# Trigger.net
KiCad netlist of a schematic drawn in Altium Designer
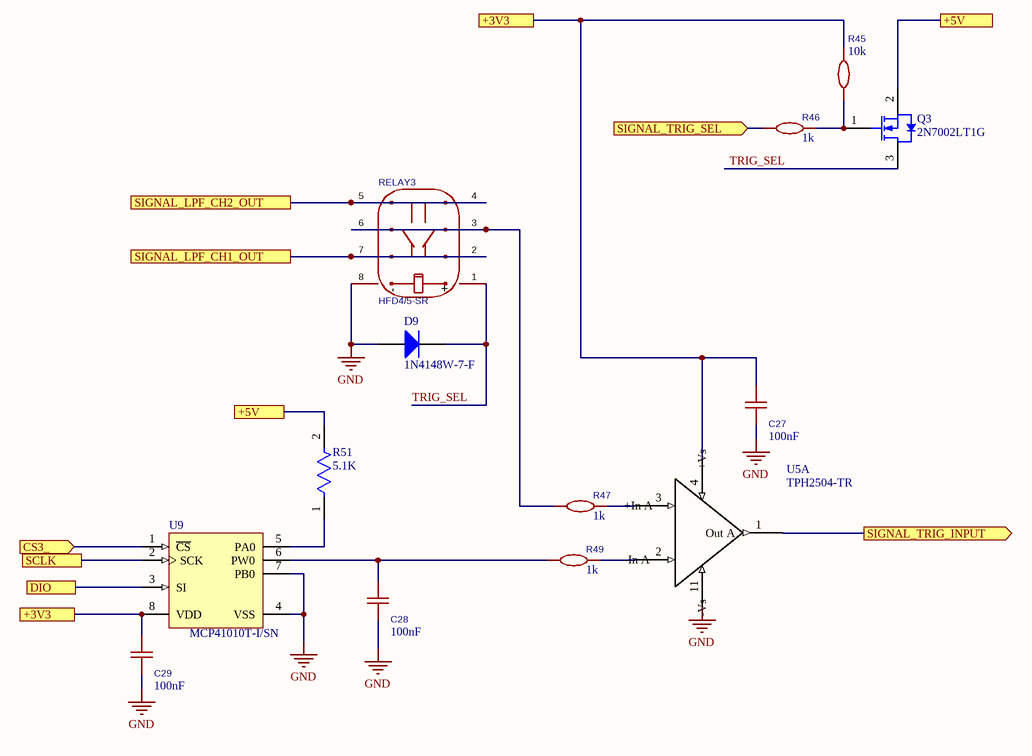
[diagram p0: Trigger.SchDoc]

(export (version "E")
  (design (tool "Eeschema 10.0.6"))
  (components
    (comp (ref "C27")
      (value "100nF")
      (footprint "C0805")
      (description "Capacitance:100nF Tolerance:±5% Tolerance:±5% Voltage Rating:50V Temperature Coefficient:X7R")
      (fields (field (name "MANUFACTURER") "YAGEO(国巨)") (field (name "TOLERANCE") "5%"))
      (libsource (lib "zhiming xue") (part "0805CG6R0C500NT_C67560"))
    )
    (comp (ref "C28")
      (value "100nF")
      (footprint "C0805")
      (description "Capacitance:100nF Tolerance:±5% Tolerance:±5% Voltage Rating:50V Temperature Coefficient:X7R")
      (fields (field (name "MANUFACTURER") "YAGEO(国巨)") (field (name "TOLERANCE") "5%"))
      (libsource (lib "zhiming xue") (part "0805CG6R0C500NT_C67560"))
    )
    (comp (ref "C29")
      (value "100nF")
      (footprint "C0805")
      (description "Capacitance:100nF Tolerance:±5% Tolerance:±5% Voltage Rating:50V Temperature Coefficient:X7R")
      (fields (field (name "MANUFACTURER") "YAGEO(国巨)") (field (name "TOLERANCE") "5%"))
      (libsource (lib "zhiming xue") (part "0805CG6R0C500NT_C67560"))
    )
    (comp (ref "D9")
      (value "1N4148W-7-F")
      (footprint "DIOD-SOD123-2_V")
      (description "Fast Switching Diode, 100 V, 0.15 A, -65 to 150 degC, 2-Pin?SOD123, RoHS, Tape and Reel")
      (fields (field (name "MANUFACTURER") "Diodes Inc"))
      (libsource (lib "Altium Content Vault") (part "D-AK-2"))
    )
    (comp (ref "Q3")
      (value "2N7002LT1G")
      (footprint "ONSC-SOT-23-3-318-08_V")
      (description "Small Signal MOSFET, 60 V, 115 mA, N-Channel, 3-Pin SOT-23, Pb-Free, Tape and Reel")
      (fields (field (name "MANUFACTURER") "On Semiconductor"))
      (libsource (lib "Altium Content Vault") (part "ONSC-NMOS-G1S2D3-3"))
    )
    (comp (ref "R45")
      (value "10k")
      (footprint "R0805")
      (fields
        (field (name "MANUFACTURER") "UNI-ROYAL(厚声)")
        (field (name "TOLERANCE") "1%")
        (field (name "MANUFACTURER PART NUMBER") "0805W8F1002T5E")
      )
      (libsource (lib "zhiming xue") (part "0805W8F0000T5E_C17477"))
    )
    (comp (ref "R46")
      (value "1k")
      (footprint "R0805")
      (fields
        (field (name "MANUFACTURER") "UNI-ROYAL(厚声)")
        (field (name "TOLERANCE") "1%")
        (field (name "MANUFACTURER PART NUMBER") "0805W8F1001T5E")
      )
      (libsource (lib "zhiming xue") (part "0805W8F0000T5E_C17477"))
    )
    (comp (ref "R47")
      (value "1k")
      (footprint "R0805")
      (fields
        (field (name "MANUFACTURER") "UNI-ROYAL(厚声)")
        (field (name "TOLERANCE") "1%")
        (field (name "MANUFACTURER PART NUMBER") "0805W8F1001T5E")
      )
      (libsource (lib "zhiming xue") (part "0805W8F0000T5E_C17477"))
    )
    (comp (ref "R49")
      (value "1k")
      (footprint "R0805")
      (fields
        (field (name "MANUFACTURER") "UNI-ROYAL(厚声)")
        (field (name "TOLERANCE") "1%")
        (field (name "MANUFACTURER PART NUMBER") "0805W8F1001T5E")
      )
      (libsource (lib "zhiming xue") (part "0805W8F0000T5E_C17477"))
    )
    (comp (ref "R51")
      (value "5.1K")
      (footprint "FP-RT0805-MFG")
      (description "125mW Thin Film Resistor ±50ppm/℃ ±1% 5.1kΩ 0805 Chip Resistor - Surface Mount ROHS")
      (fields (field (name "TOLERANCE") "1%"))
      (libsource (lib "zhiming xue") (part "1029c3af85768c4190bb7ad29bc67b5"))
    )
    (comp (ref "RELAY3")
      (value "HFD4/5-SR")
      (footprint "RELAY-SMD_HFD4-5-SR")
      (fields (field (name "MANUFACTURER") "HF(宏发)"))
      (libsource (lib "zhiming xue") (part "HFD4/5-SR"))
    )
    (comp (ref "U5")
      (value "TPH2504-TR")
      (footprint "TSOP65P640X120-14N")
      (description "Operational Amplifier, 4 Func, 5000uV Offset-Max, CMOS, PDSO14")
      (libsource (lib "zhiming xue") (part "TPH2504-TR-Symbol-1"))
    )
    (comp (ref "U9")
      (value "MCP41010T-I/SN")
      (footprint "SOIC-SN8_M")
      (libsource (lib "Altium Content Vault") (part "IN-DPOT-MCP41XXX-8"))
    )
  )
  (nets
    (net (code "1") (name "/+3V3") (class "Default")
      (node (ref "C27") (pin "1") (pinfunction "1_1") (pintype "passive"))
      (node (ref "C29") (pin "1") (pinfunction "1_1") (pintype "passive"))
      (node (ref "R45") (pin "2") (pinfunction "2_2") (pintype "passive"))
      (node (ref "U5") (pin "4") (pinfunction "+Vs_4") (pintype "input"))
      (node (ref "U9") (pin "8") (pinfunction "VDD_8") (pintype "power_in"))
    )
    (net (code "2") (name "/+5V") (class "Default")
      (node (ref "Q3") (pin "2") (pinfunction "S_2") (pintype "passive"))
      (node (ref "R51") (pin "2") (pinfunction "2_2") (pintype "passive"))
    )
    (net (code "3") (name "/CS3_") (class "Default")
      (node (ref "U9") (pin "1") (pinfunction "~{CS}_1") (pintype "input"))
    )
    (net (code "4") (name "/DIO") (class "Default")
      (node (ref "U9") (pin "3") (pinfunction "SI_3") (pintype "input"))
    )
    (net (code "5") (name "/SCLK") (class "Default")
      (node (ref "U9") (pin "2") (pinfunction "SCK_2") (pintype "input"))
    )
    (net (code "6") (name "/SIGNAL_LPF_CH1_OUT") (class "Default")
      (node (ref "RELAY3") (pin "2") (pinfunction "2_2") (pintype "passive"))
      (node (ref "RELAY3") (pin "7") (pinfunction "7_7") (pintype "passive"))
    )
    (net (code "7") (name "/SIGNAL_LPF_CH2_OUT") (class "Default")
      (node (ref "RELAY3") (pin "4") (pinfunction "4_4") (pintype "passive"))
      (node (ref "RELAY3") (pin "5") (pinfunction "5_5") (pintype "passive"))
    )
    (net (code "8") (name "/SIGNAL_TRIG_INPUT") (class "Default")
      (node (ref "U5") (pin "1") (pinfunction "Out_A_1") (pintype "output"))
    )
    (net (code "9") (name "/SIGNAL_TRIG_SEL") (class "Default")
      (node (ref "R46") (pin "1") (pinfunction "1_1") (pintype "passive"))
    )
    (net (code "10") (name "/TRIG_SEL") (class "Default")
      (node (ref "D9") (pin "2") (pinfunction "K_2") (pintype "passive"))
      (node (ref "Q3") (pin "3") (pinfunction "D_3") (pintype "passive"))
      (node (ref "RELAY3") (pin "1") (pinfunction "1_1") (pintype "passive"))
    )
    (net (code "11") (name "GND") (class "Default")
      (node (ref "C27") (pin "2") (pinfunction "2_2") (pintype "passive"))
      (node (ref "C28") (pin "2") (pinfunction "2_2") (pintype "passive"))
      (node (ref "C29") (pin "2") (pinfunction "2_2") (pintype "passive"))
      (node (ref "D9") (pin "1") (pinfunction "A_1") (pintype "passive"))
      (node (ref "RELAY3") (pin "8") (pinfunction "8_8") (pintype "passive"))
      (node (ref "U5") (pin "11") (pinfunction "-Vs_11") (pintype "input"))
      (node (ref "U9") (pin "4") (pinfunction "VSS_4") (pintype "power_in"))
      (node (ref "U9") (pin "7") (pinfunction "PB0_7") (pintype "passive"))
    )
    (net (code "12") (name "Net-(Q3-G)") (class "Default")
      (node (ref "Q3") (pin "1") (pinfunction "G_1") (pintype "passive"))
      (node (ref "R45") (pin "1") (pinfunction "1_1") (pintype "passive"))
      (node (ref "R46") (pin "2") (pinfunction "2_2") (pintype "passive"))
    )
    (net (code "13") (name "Net-(R47-Pad1)") (class "Default")
      (node (ref "R47") (pin "1") (pinfunction "1_1") (pintype "passive"))
      (node (ref "RELAY3") (pin "3") (pinfunction "3_3") (pintype "passive"))
      (node (ref "RELAY3") (pin "6") (pinfunction "6_6") (pintype "passive"))
    )
    (net (code "14") (name "Net-(U5A-+In_A)") (class "Default")
      (node (ref "R47") (pin "2") (pinfunction "2_2") (pintype "passive"))
      (node (ref "U5") (pin "3") (pinfunction "+In_A_3") (pintype "input"))
    )
    (net (code "15") (name "Net-(U5A--In_A)") (class "Default")
      (node (ref "R49") (pin "2") (pinfunction "2_2") (pintype "passive"))
      (node (ref "U5") (pin "2") (pinfunction "-In_A_2") (pintype "input"))
    )
    (net (code "16") (name "Net-(U9-PA0)") (class "Default")
      (node (ref "R51") (pin "1") (pinfunction "1_1") (pintype "passive"))
      (node (ref "U9") (pin "5") (pinfunction "PA0_5") (pintype "passive"))
    )
    (net (code "17") (name "Net-(U9-PW0)") (class "Default")
      (node (ref "C28") (pin "1") (pinfunction "1_1") (pintype "passive"))
      (node (ref "R49") (pin "1") (pinfunction "1_1") (pintype "passive"))
      (node (ref "U9") (pin "6") (pinfunction "PW0_6") (pintype "passive"))
    )
  )
)
